# SCH_Workshop-components_2025-10-19.net
KiCad netlist of a schematic drawn in EasyEDA
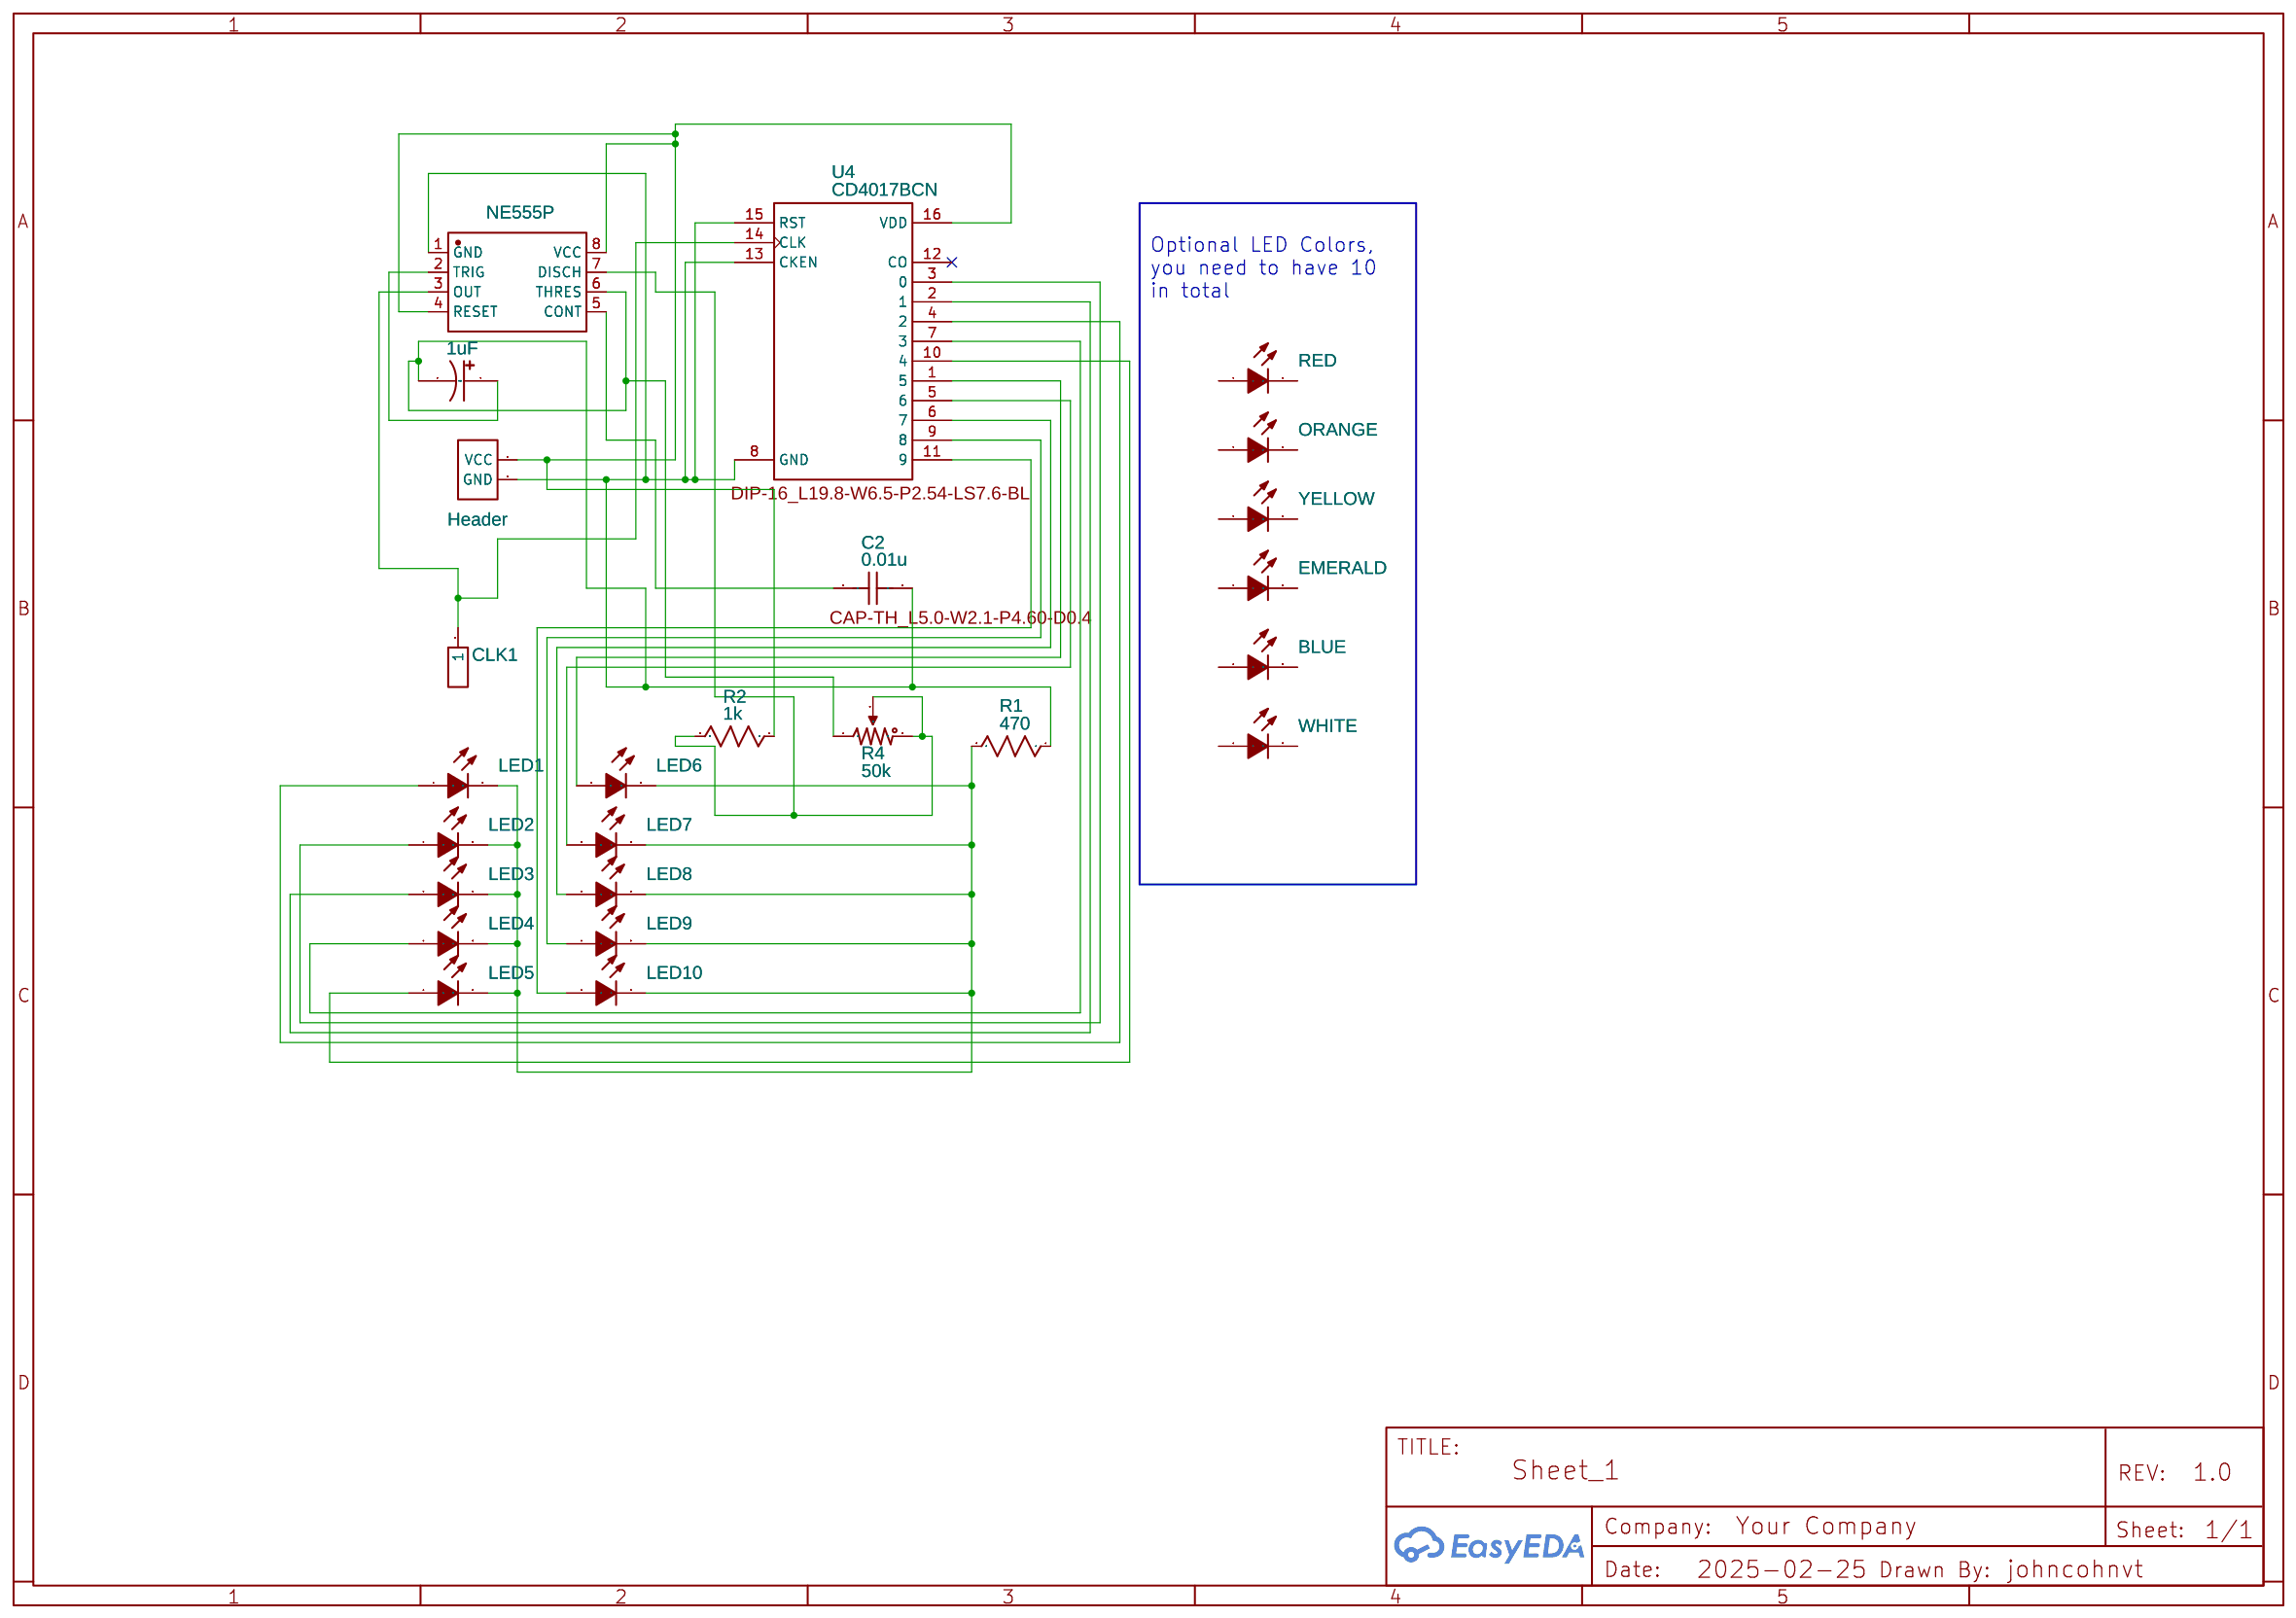
[diagram p0: schematic sheet]

(export (version "E")
  (design (tool "Eeschema 10.0.6"))
  (components
    (comp (ref "BLUE") (value "LED_5MM") (libsource (lib "") (part "LED_5MM_2")))
    (comp (ref "C1")
      (value "1uF")
      (fields (field (name "Manufacturer Part") "UVZ1H010MDD") (field (name "Manufacturer") "Nichicon(尼吉康)"))
      (libsource (lib "") (part "UVZ1H010MDD"))
    )
    (comp (ref "C2") (value "0.01u") (libsource (lib "") (part "C_0603_US")))
    (comp (ref "CLK1")
      (value "C81276")
      (fields
        (field (name "Manufacturer Part") "2.54-1*1P针")
        (field (name "Manufacturer") "BOOMELE(Boom Precision Elec)")
      )
      (libsource (lib "") (part "Header-Male-2.54_1x1"))
    )
    (comp (ref "EMERALD") (value "LED_5MM") (libsource (lib "") (part "LED_5MM_6")))
    (comp (ref "H1") (value "Header") (libsource (lib "") (part "HEADER-FEMALE-2.54_1X2")))
    (comp (ref "LED1") (value "LED_5MM") (libsource (lib "") (part "LED_5MM")))
    (comp (ref "LED2") (value "LED_5MM") (libsource (lib "") (part "LED_5MM")))
    (comp (ref "LED3") (value "LED_5MM") (libsource (lib "") (part "LED_5MM")))
    (comp (ref "LED4") (value "LED_5MM") (libsource (lib "") (part "LED_5MM")))
    (comp (ref "LED5") (value "LED_5MM") (libsource (lib "") (part "LED_5MM")))
    (comp (ref "LED6") (value "LED_5MM") (libsource (lib "") (part "LED_5MM")))
    (comp (ref "LED7") (value "LED_5MM") (libsource (lib "") (part "LED_5MM")))
    (comp (ref "LED8") (value "LED_5MM") (libsource (lib "") (part "LED_5MM")))
    (comp (ref "LED9") (value "LED_5MM") (libsource (lib "") (part "LED_5MM")))
    (comp (ref "LED10") (value "LED_5MM") (libsource (lib "") (part "LED_5MM")))
    (comp (ref "ORANGE") (value "LED_5MM") (libsource (lib "") (part "LED_5MM_5")))
    (comp (ref "R1")
      (value "470")
      (fields (field (name "Manufacturer Part") "?"))
      (libsource (lib "") (part "Resistor"))
    )
    (comp (ref "R2")
      (value "1k")
      (fields (field (name "Manufacturer Part") "?"))
      (libsource (lib "") (part "Resistor"))
    )
    (comp (ref "R4")
      (value "50k")
      (fields (field (name "Manufacturer Part") "?"))
      (libsource (lib "") (part "Potentiometer"))
    )
    (comp (ref "RED") (value "LED_5MM") (libsource (lib "") (part "LED_5MM_3")))
    (comp (ref "U2")
      (value "NE555P")
      (fields (field (name "Manufacturer") "TI(德州仪器)"))
      (libsource (lib "") (part "NE555P"))
    )
    (comp (ref "U4") (value "CD4017BCN") (libsource (lib "") (part "CD4017BCN")))
    (comp (ref "WHITE") (value "LED_5MM") (libsource (lib "") (part "LED_5MM_4")))
    (comp (ref "YELLOW") (value "LED_5MM") (libsource (lib "") (part "LED_5MM_1")))
  )
  (nets
    (net (code "1") (name "Net-(H1-GND)") (class "Default")
      (node (ref "C1") (pin "2") (pinfunction "2_2") (pintype "unspecified"))
      (node (ref "C2") (pin "2") (pinfunction "2_2") (pintype "unspecified"))
      (node (ref "H1") (pin "2") (pinfunction "GND_2") (pintype "unspecified"))
      (node (ref "R1") (pin "1") (pinfunction "1_1") (pintype "unspecified"))
      (node (ref "R4") (pin "1") (pinfunction "1_1") (pintype "unspecified"))
      (node (ref "U2") (pin "1") (pinfunction "GND_1") (pintype "unspecified"))
      (node (ref "U2") (pin "6") (pinfunction "THRES_6") (pintype "unspecified"))
      (node (ref "U4") (pin "13") (pinfunction "CKEN_13") (pintype "unspecified"))
      (node (ref "U4") (pin "15") (pinfunction "RST_15") (pintype "unspecified"))
      (node (ref "U4") (pin "8") (pinfunction "GND_8") (pintype "passive"))
    )
    (net (code "2") (name "Net-(H1-VCC)") (class "Default")
      (node (ref "H1") (pin "1") (pinfunction "VCC_1") (pintype "unspecified"))
      (node (ref "R2") (pin "1") (pinfunction "1_1") (pintype "unspecified"))
      (node (ref "U2") (pin "4") (pinfunction "RESET_4") (pintype "unspecified"))
      (node (ref "U2") (pin "8") (pinfunction "VCC_8") (pintype "unspecified"))
      (node (ref "U4") (pin "16") (pinfunction "VDD_16") (pintype "passive"))
    )
    (net (code "3") (name "Net-(LED1-A)") (class "Default")
      (node (ref "LED1") (pin "1") (pinfunction "A_1") (pintype "input"))
      (node (ref "U4") (pin "4") (pinfunction "2_4") (pintype "output"))
    )
    (net (code "4") (name "Net-(LED1-K)") (class "Default")
      (node (ref "LED1") (pin "2") (pinfunction "K_2") (pintype "input"))
      (node (ref "LED10") (pin "2") (pinfunction "K_2") (pintype "input"))
      (node (ref "LED2") (pin "2") (pinfunction "K_2") (pintype "input"))
      (node (ref "LED3") (pin "2") (pinfunction "K_2") (pintype "input"))
      (node (ref "LED4") (pin "2") (pinfunction "K_2") (pintype "input"))
      (node (ref "LED5") (pin "2") (pinfunction "K_2") (pintype "input"))
      (node (ref "LED6") (pin "2") (pinfunction "K_2") (pintype "input"))
      (node (ref "LED7") (pin "2") (pinfunction "K_2") (pintype "input"))
      (node (ref "LED8") (pin "2") (pinfunction "K_2") (pintype "input"))
      (node (ref "LED9") (pin "2") (pinfunction "K_2") (pintype "input"))
      (node (ref "R1") (pin "2") (pinfunction "2_2") (pintype "unspecified"))
    )
    (net (code "5") (name "Net-(LED2-A)") (class "Default")
      (node (ref "LED2") (pin "1") (pinfunction "A_1") (pintype "input"))
      (node (ref "U4") (pin "3") (pinfunction "0_3") (pintype "output"))
    )
    (net (code "6") (name "Net-(LED3-A)") (class "Default")
      (node (ref "LED3") (pin "1") (pinfunction "A_1") (pintype "input"))
      (node (ref "U4") (pin "2") (pinfunction "1_2") (pintype "output"))
    )
    (net (code "7") (name "Net-(LED4-A)") (class "Default")
      (node (ref "LED4") (pin "1") (pinfunction "A_1") (pintype "input"))
      (node (ref "U4") (pin "7") (pinfunction "3_7") (pintype "output"))
    )
    (net (code "8") (name "Net-(LED5-A)") (class "Default")
      (node (ref "LED5") (pin "1") (pinfunction "A_1") (pintype "input"))
      (node (ref "U4") (pin "10") (pinfunction "4_10") (pintype "output"))
    )
    (net (code "9") (name "Net-(LED6-A)") (class "Default")
      (node (ref "LED6") (pin "1") (pinfunction "A_1") (pintype "input"))
      (node (ref "U4") (pin "1") (pinfunction "5_1") (pintype "output"))
    )
    (net (code "10") (name "Net-(LED7-A)") (class "Default")
      (node (ref "LED7") (pin "1") (pinfunction "A_1") (pintype "input"))
      (node (ref "U4") (pin "5") (pinfunction "6_5") (pintype "output"))
    )
    (net (code "11") (name "Net-(LED8-A)") (class "Default")
      (node (ref "LED8") (pin "1") (pinfunction "A_1") (pintype "input"))
      (node (ref "U4") (pin "6") (pinfunction "7_6") (pintype "output"))
    )
    (net (code "12") (name "Net-(LED9-A)") (class "Default")
      (node (ref "LED9") (pin "1") (pinfunction "A_1") (pintype "input"))
      (node (ref "U4") (pin "9") (pinfunction "8_9") (pintype "output"))
    )
    (net (code "13") (name "Net-(LED10-A)") (class "Default")
      (node (ref "LED10") (pin "1") (pinfunction "A_1") (pintype "input"))
      (node (ref "U4") (pin "11") (pinfunction "9_11") (pintype "output"))
    )
    (net (code "14") (name "Net-(R4-2)") (class "Default")
      (node (ref "R2") (pin "2") (pinfunction "2_2") (pintype "unspecified"))
      (node (ref "R4") (pin "2") (pinfunction "3_2") (pintype "unspecified"))
      (node (ref "R4") (pin "3") (pinfunction "2_3") (pintype "unspecified"))
      (node (ref "U2") (pin "7") (pinfunction "DISCH_7") (pintype "unspecified"))
    )
    (net (code "15") (name "Net-(U2-CONT)") (class "Default")
      (node (ref "C2") (pin "1") (pinfunction "1_1") (pintype "unspecified"))
      (node (ref "U2") (pin "5") (pinfunction "CONT_5") (pintype "unspecified"))
    )
    (net (code "16") (name "Net-(U2-OUT)") (class "Default")
      (node (ref "CLK1") (pin "1") (pinfunction "1_1") (pintype "unspecified"))
      (node (ref "U2") (pin "3") (pinfunction "OUT_3") (pintype "unspecified"))
      (node (ref "U4") (pin "14") (pinfunction "CLK_14") (pintype "unspecified"))
    )
    (net (code "17") (name "Net-(U2-TRIG)") (class "Default")
      (node (ref "C1") (pin "1") (pinfunction "1_1") (pintype "unspecified"))
      (node (ref "U2") (pin "2") (pinfunction "TRIG_2") (pintype "unspecified"))
    )
    (net (code "18") (name "unconnected-(BLUE-A-Pad1)") (class "Default")
      (node (ref "BLUE") (pin "1") (pinfunction "A_1") (pintype "input"))
    )
    (net (code "19") (name "unconnected-(BLUE-K-Pad2)") (class "Default")
      (node (ref "BLUE") (pin "2") (pinfunction "K_2") (pintype "input"))
    )
    (net (code "20") (name "unconnected-(EMERALD-A-Pad1)") (class "Default")
      (node (ref "EMERALD") (pin "1") (pinfunction "A_1") (pintype "input"))
    )
    (net (code "21") (name "unconnected-(EMERALD-K-Pad2)") (class "Default")
      (node (ref "EMERALD") (pin "2") (pinfunction "K_2") (pintype "input"))
    )
    (net (code "22") (name "unconnected-(ORANGE-A-Pad1)") (class "Default")
      (node (ref "ORANGE") (pin "1") (pinfunction "A_1") (pintype "input"))
    )
    (net (code "23") (name "unconnected-(ORANGE-K-Pad2)") (class "Default")
      (node (ref "ORANGE") (pin "2") (pinfunction "K_2") (pintype "input"))
    )
    (net (code "24") (name "unconnected-(RED-A-Pad1)") (class "Default")
      (node (ref "RED") (pin "1") (pinfunction "A_1") (pintype "input"))
    )
    (net (code "25") (name "unconnected-(RED-K-Pad2)") (class "Default")
      (node (ref "RED") (pin "2") (pinfunction "K_2") (pintype "input"))
    )
    (net (code "26") (name "unconnected-(U4-CO-Pad12)") (class "Default")
      (node (ref "U4") (pin "12") (pinfunction "CO_12") (pintype "output+no_connect"))
    )
    (net (code "27") (name "unconnected-(WHITE-A-Pad1)") (class "Default")
      (node (ref "WHITE") (pin "1") (pinfunction "A_1") (pintype "input"))
    )
    (net (code "28") (name "unconnected-(WHITE-K-Pad2)") (class "Default")
      (node (ref "WHITE") (pin "2") (pinfunction "K_2") (pintype "input"))
    )
    (net (code "29") (name "unconnected-(YELLOW-A-Pad1)") (class "Default")
      (node (ref "YELLOW") (pin "1") (pinfunction "A_1") (pintype "input"))
    )
    (net (code "30") (name "unconnected-(YELLOW-K-Pad2)") (class "Default")
      (node (ref "YELLOW") (pin "2") (pinfunction "K_2") (pintype "input"))
    )
  )
)
